# Power.net
KiCad netlist of a schematic drawn in Altium Designer
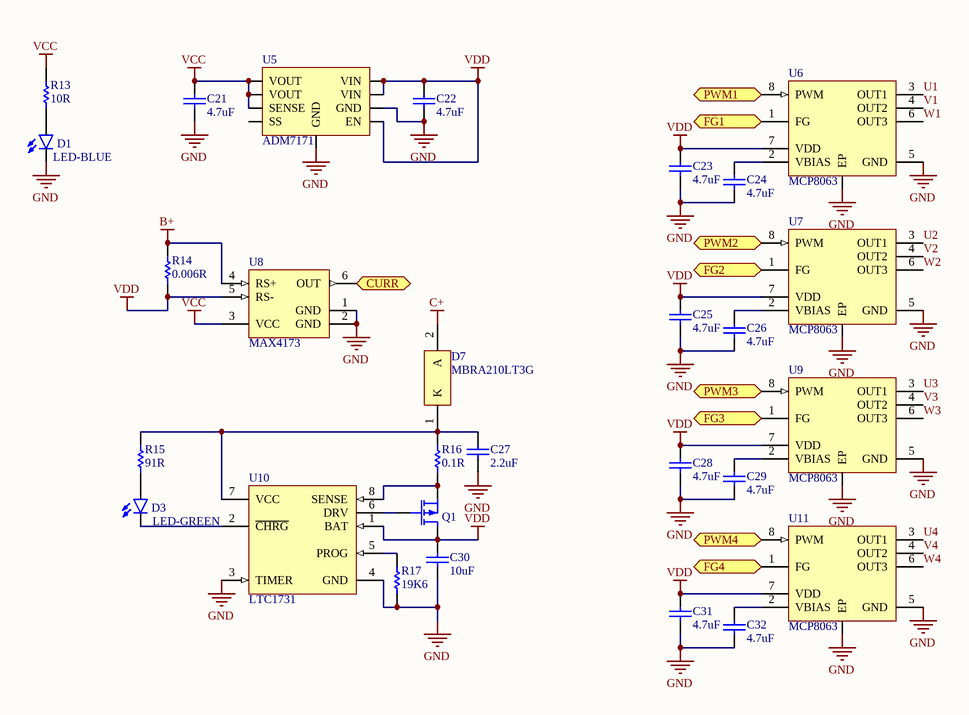
[diagram p0: Power.SchDoc]

(export (version "E")
  (design (tool "Eeschema 10.0.6"))
  (components
    (comp (ref "C21")
      (value "4.7uF")
      (footprint "CAPC0402(1005)60_L")
      (description "CAP 4.7uF 6.3V ±10% 0402 (1005 Metric) Thickness 0.6mm SMD")
      (fields (field (name "TOLERANCE") "Â±10%"))
      (libsource (lib "Altium Content Vault") (part "CAP"))
    )
    (comp (ref "C22")
      (value "4.7uF")
      (footprint "CAPC0402(1005)60_L")
      (description "CAP 4.7uF 6.3V ±10% 0402 (1005 Metric) Thickness 0.6mm SMD")
      (fields (field (name "TOLERANCE") "Â±10%"))
      (libsource (lib "Altium Content Vault") (part "CAP"))
    )
    (comp (ref "C23")
      (value "4.7uF")
      (footprint "CAPC0402(1005)60_L")
      (description "CAP 4.7uF 6.3V ±10% 0402 (1005 Metric) Thickness 0.6mm SMD")
      (fields (field (name "TOLERANCE") "Â±10%"))
      (libsource (lib "Altium Content Vault") (part "CAP"))
    )
    (comp (ref "C24")
      (value "4.7uF")
      (footprint "CAPC0402(1005)60_L")
      (description "CAP 4.7uF 6.3V ±10% 0402 (1005 Metric) Thickness 0.6mm SMD")
      (fields (field (name "TOLERANCE") "Â±10%"))
      (libsource (lib "Altium Content Vault") (part "CAP"))
    )
    (comp (ref "C25")
      (value "4.7uF")
      (footprint "CAPC0402(1005)60_L")
      (description "CAP 4.7uF 6.3V ±10% 0402 (1005 Metric) Thickness 0.6mm SMD")
      (fields (field (name "TOLERANCE") "Â±10%"))
      (libsource (lib "Altium Content Vault") (part "CAP"))
    )
    (comp (ref "C26")
      (value "4.7uF")
      (footprint "CAPC0402(1005)60_L")
      (description "CAP 4.7uF 6.3V ±10% 0402 (1005 Metric) Thickness 0.6mm SMD")
      (fields (field (name "TOLERANCE") "Â±10%"))
      (libsource (lib "Altium Content Vault") (part "CAP"))
    )
    (comp (ref "C27")
      (value "2.2uF")
      (footprint "CAPC0402(1005)60_M")
      (description "CAP 2.2uF 6.3V ±10% 0402 (1005 Metric) Thickness 0.6mm SMD")
      (fields (field (name "TOLERANCE") "Â±10%"))
      (libsource (lib "Altium Content Vault") (part "CAP"))
    )
    (comp (ref "C28")
      (value "4.7uF")
      (footprint "CAPC0402(1005)60_L")
      (description "CAP 4.7uF 6.3V ±10% 0402 (1005 Metric) Thickness 0.6mm SMD")
      (fields (field (name "TOLERANCE") "Â±10%"))
      (libsource (lib "Altium Content Vault") (part "CAP"))
    )
    (comp (ref "C29")
      (value "4.7uF")
      (footprint "CAPC0402(1005)60_L")
      (description "CAP 4.7uF 6.3V ±10% 0402 (1005 Metric) Thickness 0.6mm SMD")
      (fields (field (name "TOLERANCE") "Â±10%"))
      (libsource (lib "Altium Content Vault") (part "CAP"))
    )
    (comp (ref "C30")
      (value "10uF")
      (footprint "CAPC0402(1005)60_N")
      (description "CAP 10uF 6.3V ±20% 0402 (1005 Metric) Thickness 0.6mm SMD")
      (fields (field (name "TOLERANCE") "Â±20%"))
      (libsource (lib "Altium Content Vault") (part "CAP"))
    )
    (comp (ref "C31")
      (value "4.7uF")
      (footprint "CAPC0402(1005)60_L")
      (description "CAP 4.7uF 6.3V ±10% 0402 (1005 Metric) Thickness 0.6mm SMD")
      (fields (field (name "TOLERANCE") "Â±10%"))
      (libsource (lib "Altium Content Vault") (part "CAP"))
    )
    (comp (ref "C32")
      (value "4.7uF")
      (footprint "CAPC0402(1005)60_L")
      (description "CAP 4.7uF 6.3V ±10% 0402 (1005 Metric) Thickness 0.6mm SMD")
      (fields (field (name "TOLERANCE") "Â±10%"))
      (libsource (lib "Altium Content Vault") (part "CAP"))
    )
    (comp (ref "D1")
      (value "LED-BLUE")
      (footprint "LED-1206")
      (libsource (lib "Components") (part "LED-BLUE1206"))
    )
    (comp (ref "D3")
      (value "LED-GREEN")
      (footprint "LED-1206")
      (libsource (lib "Components") (part "LED-GREEN1206"))
    )
    (comp (ref "D7")
      (value "MBRA210LT3G")
      (footprint "ONSC-SMA-2-403D-02_F_V")
      (description "Schottky Power Rectifier, 2-Pin SMA, Pb-Free, Tape and Reel")
      (fields (field (name "MANUFACTURER") "On Semiconductor"))
      (libsource (lib "Altium Content Vault") (part "ONSC-D-K1A2-2_A"))
    )
    (comp (ref "Q1")
      (value "MOSFET-P")
      (footprint "SOT23-3")
      (description "P-Channel MOSFET")
      (fields (field (name "PUBLISHER") "Altium Limited"))
      (libsource (lib "Components") (part "MOSFET-P"))
    )
    (comp (ref "R13")
      (value "10R")
      (footprint "RESC0402(1005)_N")
      (description "10R 0.063W 5% 0402 (1005 Metric)  SMD")
      (fields (field (name "POWER") "0.063 W") (field (name "TOLERANCE") "5 %"))
      (libsource (lib "Altium Content Vault") (part "RES"))
    )
    (comp (ref "R14")
      (value "0.006R")
      (footprint "RESC0805(2012)_N")
      (description "Jumper 0805 (2012 Metric)")
      (fields (field (name "TOLERANCE") "None"))
      (libsource (lib "Altium Content Vault") (part "RES"))
    )
    (comp (ref "R15")
      (value "91R")
      (footprint "RESC0402(1005)_M")
      (description "91R 0.063W 5% 0402 (1005 Metric)  SMD")
      (fields (field (name "POWER") "0.063 W") (field (name "TOLERANCE") "5 %"))
      (libsource (lib "Altium Content Vault") (part "RES"))
    )
    (comp (ref "R16")
      (value "0.1R")
      (footprint "RESC0603(1608)_M")
      (description "1R 0.1W 5% 0603 (1608 Metric)  SMD")
      (fields (field (name "POWER") "0.1 W") (field (name "TOLERANCE") "5 %"))
      (libsource (lib "Altium Content Vault") (part "RES"))
    )
    (comp (ref "R17")
      (value "19K6")
      (footprint "RESC0402(1005)_M")
      (description "20K 0.063W 5% 0402 (1005 Metric)  SMD")
      (fields (field (name "TOLERANCE") "5 %") (field (name "POWER") "0.063 W"))
      (libsource (lib "Altium Content Vault") (part "CMP-1011-00105-1"))
    )
    (comp (ref "U5")
      (value "ADM7171")
      (footprint "SON50P300X85_HS-9N")
      (libsource (lib "Components") (part "ADM7171"))
    )
    (comp (ref "U6")
      (value "MCP8063")
      (footprint "DFN8")
      (fields (field (name "PARTNUMBER") "MTD6501G-HC1") (field (name "MANUFACTURER") "Microchip"))
      (libsource (lib "Components") (part "MCP8063"))
    )
    (comp (ref "U7")
      (value "MCP8063")
      (footprint "DFN8")
      (fields (field (name "PARTNUMBER") "MTD6501G-HC1") (field (name "MANUFACTURER") "Microchip"))
      (libsource (lib "Components") (part "MCP8063"))
    )
    (comp (ref "U8")
      (value "MAX4173")
      (footprint "MAXM-U6+1_N")
      (fields (field (name "PARTNUMBER") "MAX4173FEUT+T"))
      (libsource (lib "Altium Content Vault") (part "CMP-0252-00331-1"))
    )
    (comp (ref "U9")
      (value "MCP8063")
      (footprint "DFN8")
      (fields (field (name "PARTNUMBER") "MTD6501G-HC1") (field (name "MANUFACTURER") "Microchip"))
      (libsource (lib "Components") (part "MCP8063"))
    )
    (comp (ref "U10")
      (value "LTC1731")
      (footprint "LT-MS8-8_L")
      (fields
        (field (name "PARTNUMBER") "LTC1731EMS8-4.2#TRPBF")
        (field (name "MANUFACTURER") "Linear Technology")
      )
      (libsource (lib "Altium Content Vault") (part "LT-LTC1731-4_1_4_2-8"))
    )
    (comp (ref "U11")
      (value "MCP8063")
      (footprint "DFN8")
      (fields (field (name "PARTNUMBER") "MTD6501G-HC1") (field (name "MANUFACTURER") "Microchip"))
      (libsource (lib "Components") (part "MCP8063"))
    )
  )
  (nets
    (net (code "1") (name "/CURR") (class "Default")
      (node (ref "U8") (pin "6") (pinfunction "OUT_6") (pintype "output"))
    )
    (net (code "2") (name "/FG1") (class "Default")
      (node (ref "U6") (pin "1") (pinfunction "FG_1") (pintype "tri_state"))
    )
    (net (code "3") (name "/FG2") (class "Default")
      (node (ref "U7") (pin "1") (pinfunction "FG_1") (pintype "tri_state"))
    )
    (net (code "4") (name "/FG3") (class "Default")
      (node (ref "U9") (pin "1") (pinfunction "FG_1") (pintype "tri_state"))
    )
    (net (code "5") (name "/FG4") (class "Default")
      (node (ref "U11") (pin "1") (pinfunction "FG_1") (pintype "tri_state"))
    )
    (net (code "6") (name "/PWM1") (class "Default")
      (node (ref "U6") (pin "8") (pinfunction "PWM_8") (pintype "input"))
    )
    (net (code "7") (name "/PWM2") (class "Default")
      (node (ref "U7") (pin "8") (pinfunction "PWM_8") (pintype "input"))
    )
    (net (code "8") (name "/PWM3") (class "Default")
      (node (ref "U9") (pin "8") (pinfunction "PWM_8") (pintype "input"))
    )
    (net (code "9") (name "/PWM4") (class "Default")
      (node (ref "U11") (pin "8") (pinfunction "PWM_8") (pintype "input"))
    )
    (net (code "10") (name "/U1") (class "Default")
      (node (ref "U6") (pin "3") (pinfunction "OUT1_3") (pintype "tri_state"))
    )
    (net (code "11") (name "/U2") (class "Default")
      (node (ref "U7") (pin "3") (pinfunction "OUT1_3") (pintype "tri_state"))
    )
    (net (code "12") (name "/U3") (class "Default")
      (node (ref "U9") (pin "3") (pinfunction "OUT1_3") (pintype "tri_state"))
    )
    (net (code "13") (name "/U4") (class "Default")
      (node (ref "U11") (pin "3") (pinfunction "OUT1_3") (pintype "tri_state"))
    )
    (net (code "14") (name "/V1") (class "Default")
      (node (ref "U6") (pin "4") (pinfunction "OUT2_4") (pintype "tri_state"))
    )
    (net (code "15") (name "/V2") (class "Default")
      (node (ref "U7") (pin "4") (pinfunction "OUT2_4") (pintype "tri_state"))
    )
    (net (code "16") (name "/V3") (class "Default")
      (node (ref "U9") (pin "4") (pinfunction "OUT2_4") (pintype "tri_state"))
    )
    (net (code "17") (name "/V4") (class "Default")
      (node (ref "U11") (pin "4") (pinfunction "OUT2_4") (pintype "tri_state"))
    )
    (net (code "18") (name "/W1") (class "Default")
      (node (ref "U6") (pin "6") (pinfunction "OUT3_6") (pintype "tri_state"))
    )
    (net (code "19") (name "/W2") (class "Default")
      (node (ref "U7") (pin "6") (pinfunction "OUT3_6") (pintype "tri_state"))
    )
    (net (code "20") (name "/W3") (class "Default")
      (node (ref "U9") (pin "6") (pinfunction "OUT3_6") (pintype "tri_state"))
    )
    (net (code "21") (name "/W4") (class "Default")
      (node (ref "U11") (pin "6") (pinfunction "OUT3_6") (pintype "tri_state"))
    )
    (net (code "22") (name "B+") (class "Default")
      (node (ref "R14") (pin "2") (pinfunction "2_2") (pintype "passive"))
      (node (ref "U8") (pin "4") (pinfunction "RS+_4") (pintype "input"))
    )
    (net (code "23") (name "C+") (class "Default")
      (node (ref "D7") (pin "2") (pinfunction "A_2") (pintype "passive"))
    )
    (net (code "24") (name "GND") (class "Default")
      (node (ref "C21") (pin "1") (pinfunction "1_1") (pintype "passive"))
      (node (ref "C22") (pin "1") (pinfunction "1_1") (pintype "passive"))
      (node (ref "C23") (pin "1") (pinfunction "1_1") (pintype "passive"))
      (node (ref "C24") (pin "2") (pinfunction "2_2") (pintype "passive"))
      (node (ref "C25") (pin "1") (pinfunction "1_1") (pintype "passive"))
      (node (ref "C26") (pin "2") (pinfunction "2_2") (pintype "passive"))
      (node (ref "C27") (pin "1") (pinfunction "1_1") (pintype "passive"))
      (node (ref "C28") (pin "1") (pinfunction "1_1") (pintype "passive"))
      (node (ref "C29") (pin "2") (pinfunction "2_2") (pintype "passive"))
      (node (ref "C30") (pin "1") (pinfunction "1_1") (pintype "passive"))
      (node (ref "C31") (pin "1") (pinfunction "1_1") (pintype "passive"))
      (node (ref "C32") (pin "2") (pinfunction "2_2") (pintype "passive"))
      (node (ref "D1") (pin "C") (pinfunction "C_C") (pintype "passive"))
      (node (ref "R17") (pin "1") (pinfunction "1_1") (pintype "passive"))
      (node (ref "U10") (pin "3") (pinfunction "TIMER_3") (pintype "input"))
      (node (ref "U10") (pin "4") (pinfunction "GND_4") (pintype "power_in"))
      (node (ref "U11") (pin "5") (pinfunction "GND_5") (pintype "power_in"))
      (node (ref "U11") (pin "9") (pinfunction "EP_9") (pintype "passive"))
      (node (ref "U5") (pin "6") (pinfunction "GND_6") (pintype "passive"))
      (node (ref "U5") (pin "9") (pinfunction "GND_9") (pintype "passive"))
      (node (ref "U6") (pin "5") (pinfunction "GND_5") (pintype "power_in"))
      (node (ref "U6") (pin "9") (pinfunction "EP_9") (pintype "passive"))
      (node (ref "U7") (pin "5") (pinfunction "GND_5") (pintype "power_in"))
      (node (ref "U7") (pin "9") (pinfunction "EP_9") (pintype "passive"))
      (node (ref "U8") (pin "1") (pinfunction "GND_1") (pintype "power_in"))
      (node (ref "U8") (pin "2") (pinfunction "GND_2") (pintype "power_in"))
      (node (ref "U9") (pin "5") (pinfunction "GND_5") (pintype "power_in"))
      (node (ref "U9") (pin "9") (pinfunction "EP_9") (pintype "passive"))
    )
    (net (code "25") (name "Net-(D1-PadA)") (class "Default")
      (node (ref "D1") (pin "A") (pinfunction "A_A") (pintype "passive"))
      (node (ref "R13") (pin "1") (pinfunction "1_1") (pintype "passive"))
    )
    (net (code "26") (name "Net-(D3-PadA)") (class "Default")
      (node (ref "D3") (pin "A") (pinfunction "A_A") (pintype "passive"))
      (node (ref "R15") (pin "1") (pinfunction "1_1") (pintype "passive"))
    )
    (net (code "27") (name "Net-(D7-K)") (class "Default")
      (node (ref "C27") (pin "2") (pinfunction "2_2") (pintype "passive"))
      (node (ref "D7") (pin "1") (pinfunction "K_1") (pintype "passive"))
      (node (ref "R15") (pin "2") (pinfunction "2_2") (pintype "passive"))
      (node (ref "R16") (pin "2") (pinfunction "2_2") (pintype "passive"))
      (node (ref "U10") (pin "7") (pinfunction "VCC_7") (pintype "power_in"))
    )
    (net (code "28") (name "Net-(Q1-G)") (class "Default")
      (node (ref "Q1") (pin "1") (pinfunction "G_1") (pintype "passive"))
      (node (ref "U10") (pin "6") (pinfunction "DRV_6") (pintype "tri_state"))
    )
    (net (code "29") (name "Net-(Q1-S)") (class "Default")
      (node (ref "Q1") (pin "3") (pinfunction "S_3") (pintype "passive"))
      (node (ref "R16") (pin "1") (pinfunction "1_1") (pintype "passive"))
      (node (ref "U10") (pin "8") (pinfunction "SENSE_8") (pintype "input"))
    )
    (net (code "30") (name "Net-(U6-VBIAS)") (class "Default")
      (node (ref "C24") (pin "1") (pinfunction "1_1") (pintype "passive"))
      (node (ref "U6") (pin "2") (pinfunction "VBIAS_2") (pintype "power_in"))
    )
    (net (code "31") (name "Net-(U7-VBIAS)") (class "Default")
      (node (ref "C26") (pin "1") (pinfunction "1_1") (pintype "passive"))
      (node (ref "U7") (pin "2") (pinfunction "VBIAS_2") (pintype "power_in"))
    )
    (net (code "32") (name "Net-(U9-VBIAS)") (class "Default")
      (node (ref "C29") (pin "1") (pinfunction "1_1") (pintype "passive"))
      (node (ref "U9") (pin "2") (pinfunction "VBIAS_2") (pintype "power_in"))
    )
    (net (code "33") (name "Net-(U10-PROG)") (class "Default")
      (node (ref "R17") (pin "2") (pinfunction "2_2") (pintype "passive"))
      (node (ref "U10") (pin "5") (pinfunction "PROG_5") (pintype "input"))
    )
    (net (code "34") (name "Net-(U10-~{CHRG})") (class "Default")
      (node (ref "D3") (pin "C") (pinfunction "C_C") (pintype "passive"))
      (node (ref "U10") (pin "2") (pinfunction "~{CHRG}_2") (pintype "tri_state"))
    )
    (net (code "35") (name "Net-(U11-VBIAS)") (class "Default")
      (node (ref "C32") (pin "1") (pinfunction "1_1") (pintype "passive"))
      (node (ref "U11") (pin "2") (pinfunction "VBIAS_2") (pintype "power_in"))
    )
    (net (code "36") (name "VCC") (class "Default")
      (node (ref "C21") (pin "2") (pinfunction "2_2") (pintype "passive"))
      (node (ref "R13") (pin "2") (pinfunction "2_2") (pintype "passive"))
      (node (ref "U5") (pin "1") (pinfunction "VOUT_1") (pintype "passive"))
      (node (ref "U5") (pin "2") (pinfunction "VOUT_2") (pintype "passive"))
      (node (ref "U5") (pin "3") (pinfunction "SENSE_3") (pintype "passive"))
      (node (ref "U8") (pin "3") (pinfunction "VCC_3") (pintype "power_in"))
    )
    (net (code "37") (name "VDD") (class "Default")
      (node (ref "C22") (pin "2") (pinfunction "2_2") (pintype "passive"))
      (node (ref "C23") (pin "2") (pinfunction "2_2") (pintype "passive"))
      (node (ref "C25") (pin "2") (pinfunction "2_2") (pintype "passive"))
      (node (ref "C28") (pin "2") (pinfunction "2_2") (pintype "passive"))
      (node (ref "C30") (pin "2") (pinfunction "2_2") (pintype "passive"))
      (node (ref "C31") (pin "2") (pinfunction "2_2") (pintype "passive"))
      (node (ref "Q1") (pin "2") (pinfunction "D_2") (pintype "passive"))
      (node (ref "R14") (pin "1") (pinfunction "1_1") (pintype "passive"))
      (node (ref "U10") (pin "1") (pinfunction "BAT_1") (pintype "input"))
      (node (ref "U11") (pin "7") (pinfunction "VDD_7") (pintype "power_in"))
      (node (ref "U5") (pin "5") (pinfunction "EN_5") (pintype "passive"))
      (node (ref "U5") (pin "7") (pinfunction "VIN_7") (pintype "passive"))
      (node (ref "U5") (pin "8") (pinfunction "VIN_8") (pintype "passive"))
      (node (ref "U6") (pin "7") (pinfunction "VDD_7") (pintype "power_in"))
      (node (ref "U7") (pin "7") (pinfunction "VDD_7") (pintype "power_in"))
      (node (ref "U8") (pin "5") (pinfunction "RS-_5") (pintype "input"))
      (node (ref "U9") (pin "7") (pinfunction "VDD_7") (pintype "power_in"))
    )
    (net (code "38") (name "unconnected-(U5-SS-Pad4)") (class "Default")
      (node (ref "U5") (pin "4") (pinfunction "SS_4") (pintype "passive"))
    )
  )
)
